# USB_DebugCable.net
KiCad netlist of a schematic drawn in EAGLE
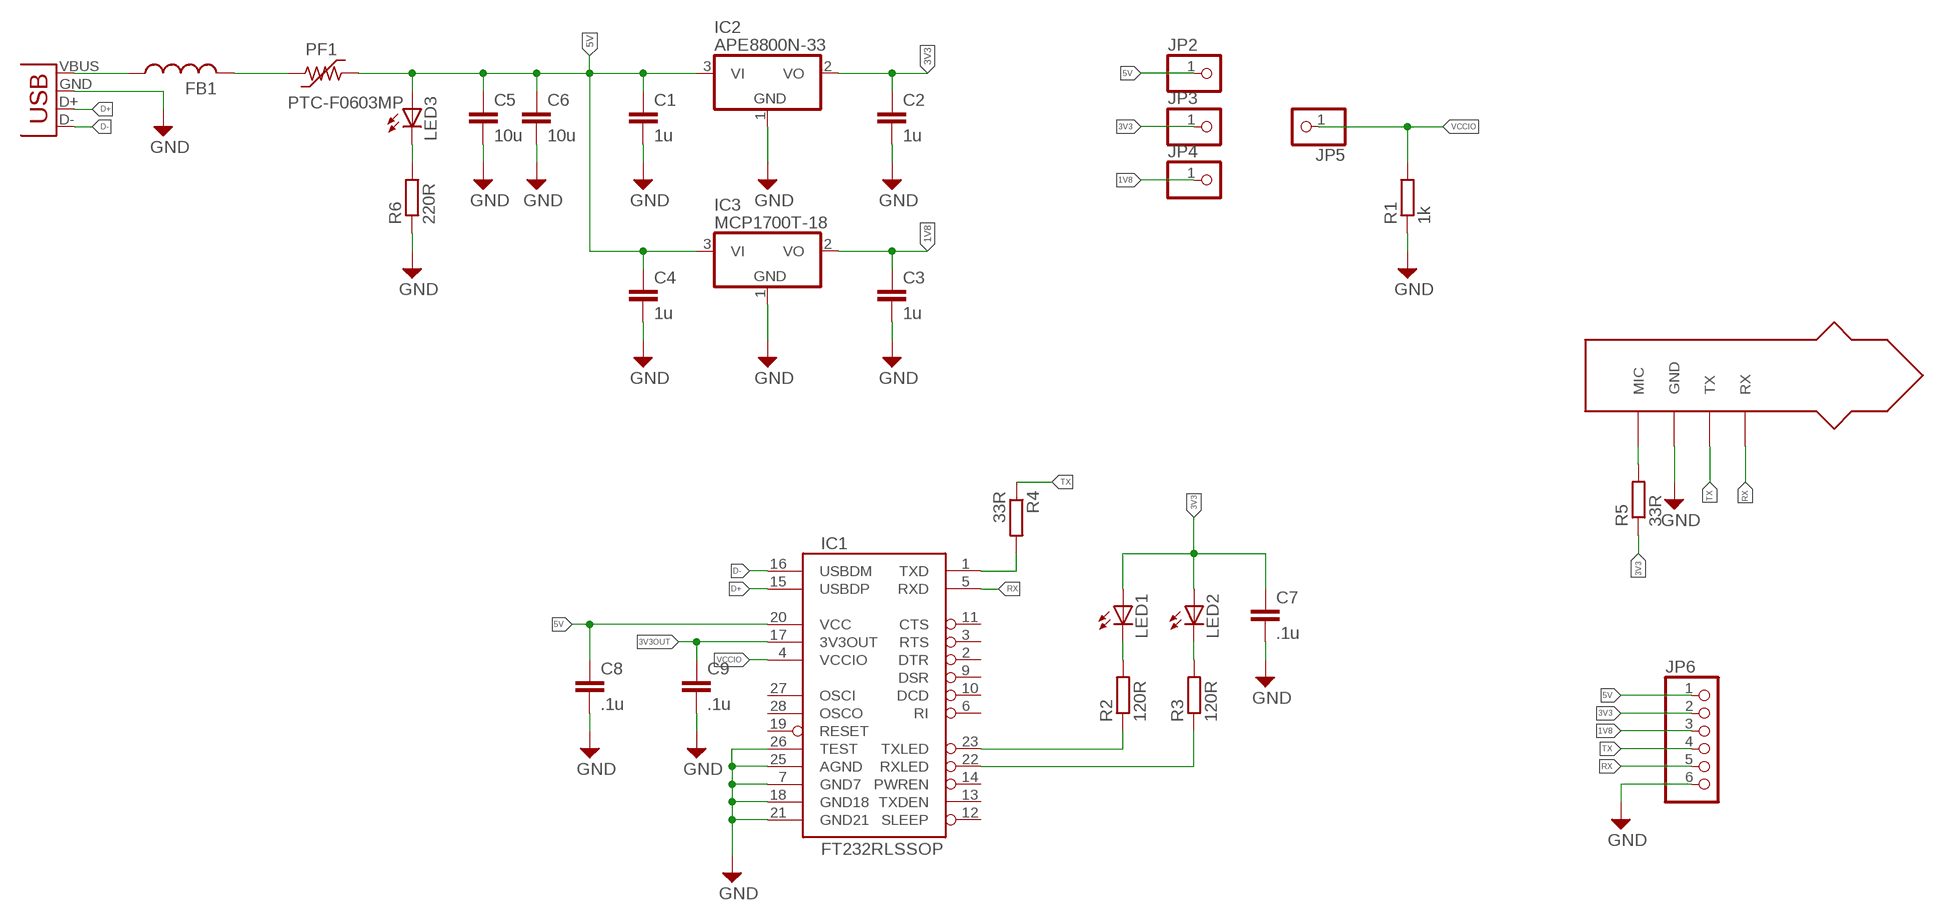
[diagram p0: schematic, sheet 1]

(export (version "E")
  (design (tool "Eeschema 10.0.6"))
  (components
    (comp (ref "C1")
      (value "1u")
      (footprint "eagle-import:C0603K")
      (libsource (lib "eagle-import") (part "C-EUC0603K"))
    )
    (comp (ref "C2")
      (value "1u")
      (footprint "eagle-import:C0603K")
      (libsource (lib "eagle-import") (part "C-EUC0603K"))
    )
    (comp (ref "C3")
      (value "1u")
      (footprint "eagle-import:C0603K")
      (libsource (lib "eagle-import") (part "C-EUC0603K"))
    )
    (comp (ref "C4")
      (value "1u")
      (footprint "eagle-import:C0603K")
      (libsource (lib "eagle-import") (part "C-EUC0603K"))
    )
    (comp (ref "C5")
      (value "10u")
      (footprint "eagle-import:C0603K")
      (libsource (lib "eagle-import") (part "C-EUC0603K"))
    )
    (comp (ref "C6")
      (value "10u")
      (footprint "eagle-import:C0603K")
      (libsource (lib "eagle-import") (part "C-EUC0603K"))
    )
    (comp (ref "C7")
      (value ".1u")
      (footprint "eagle-import:C0603K")
      (libsource (lib "eagle-import") (part "C-EUC0603K"))
    )
    (comp (ref "C8")
      (value ".1u")
      (footprint "eagle-import:C0402K")
      (libsource (lib "eagle-import") (part "C-EUC0402K"))
    )
    (comp (ref "C9")
      (value ".1u")
      (footprint "eagle-import:C0402K")
      (libsource (lib "eagle-import") (part "C-EUC0402K"))
    )
    (comp (ref "FB1")
      (value "FERRITE-BEADA")
      (footprint "eagle-import:0603")
      (libsource (lib "eagle-import") (part "FERRITE-BEADA"))
    )
    (comp (ref "IC1")
      (value "FT232RLSSOP")
      (footprint "eagle-import:SSOP28DB")
      (libsource (lib "eagle-import") (part "FT232RLSSOP"))
    )
    (comp (ref "IC2")
      (value "APE8800N-33")
      (footprint "eagle-import:SOT23")
      (libsource (lib "eagle-import") (part "MCP1703CB"))
    )
    (comp (ref "IC3")
      (value "MCP1700T-18")
      (footprint "eagle-import:SOT23")
      (libsource (lib "eagle-import") (part "MCP1703CB"))
    )
    (comp (ref "JP1")
      (value "USB-A-H")
      (footprint "eagle-import:USB-A-H")
      (libsource (lib "eagle-import") (part "USB-A-H"))
    )
    (comp (ref "JP2")
      (value "PINHD-1X1")
      (footprint "eagle-import:1X01")
      (libsource (lib "eagle-import") (part "PINHD-1X1"))
    )
    (comp (ref "JP3")
      (value "PINHD-1X1")
      (footprint "eagle-import:1X01")
      (libsource (lib "eagle-import") (part "PINHD-1X1"))
    )
    (comp (ref "JP4")
      (value "PINHD-1X1")
      (footprint "eagle-import:1X01")
      (libsource (lib "eagle-import") (part "PINHD-1X1"))
    )
    (comp (ref "JP5")
      (value "PINHD-1X1")
      (footprint "eagle-import:1X01")
      (libsource (lib "eagle-import") (part "PINHD-1X1"))
    )
    (comp (ref "JP6")
      (value "PINHD-1X6CB")
      (footprint "eagle-import:1X06-CLEANBIG")
      (libsource (lib "eagle-import") (part "PINHD-1X6CB"))
    )
    (comp (ref "LED1")
      (value "LEDCHIPLED_0603")
      (footprint "eagle-import:CHIPLED_0603")
      (libsource (lib "eagle-import") (part "LEDCHIPLED_0603"))
    )
    (comp (ref "LED2")
      (value "LEDCHIPLED_0603")
      (footprint "eagle-import:CHIPLED_0603")
      (libsource (lib "eagle-import") (part "LEDCHIPLED_0603"))
    )
    (comp (ref "LED3")
      (value "LEDCHIPLED_0603")
      (footprint "eagle-import:CHIPLED_0603")
      (libsource (lib "eagle-import") (part "LEDCHIPLED_0603"))
    )
    (comp (ref "PF1")
      (value "PTC-F0603MP")
      (footprint "eagle-import:F0603MP")
      (libsource (lib "eagle-import") (part "PTC-F0603MP"))
    )
    (comp (ref "R1")
      (value "1k")
      (footprint "eagle-import:R0603")
      (libsource (lib "eagle-import") (part "R-EU_R0603"))
    )
    (comp (ref "R2")
      (value "120R")
      (footprint "eagle-import:R0603")
      (libsource (lib "eagle-import") (part "R-EU_R0603"))
    )
    (comp (ref "R3")
      (value "120R")
      (footprint "eagle-import:R0603")
      (libsource (lib "eagle-import") (part "R-EU_R0603"))
    )
    (comp (ref "R4")
      (value "33R")
      (footprint "eagle-import:R0603")
      (libsource (lib "eagle-import") (part "R-EU_R0603"))
    )
    (comp (ref "R5")
      (value "33R")
      (footprint "eagle-import:R0603")
      (libsource (lib "eagle-import") (part "R-EU_R0603"))
    )
    (comp (ref "R6")
      (value "220R")
      (footprint "eagle-import:R0603")
      (libsource (lib "eagle-import") (part "R-EU_R0603"))
    )
    (comp (ref "U$1")
      (value "JACK3.5_4")
      (footprint "eagle-import:3.5MM4")
      (libsource (lib "eagle-import") (part "JACK3.5_4"))
    )
  )
  (nets
    (net (code "1") (name "1V8") (class "Default")
      (node (ref "C3") (pin "1") (pinfunction "1_1") (pintype "passive"))
      (node (ref "IC3") (pin "2") (pinfunction "VO_2") (pintype "passive"))
      (node (ref "JP4") (pin "1") (pinfunction "1_1") (pintype "passive"))
      (node (ref "JP6") (pin "3") (pinfunction "3_3") (pintype "passive"))
    )
    (net (code "2") (name "3V3") (class "Default")
      (node (ref "C2") (pin "1") (pinfunction "1_1") (pintype "passive"))
      (node (ref "C7") (pin "1") (pinfunction "1_1") (pintype "passive"))
      (node (ref "IC2") (pin "2") (pinfunction "VO_2") (pintype "passive"))
      (node (ref "JP3") (pin "1") (pinfunction "1_1") (pintype "passive"))
      (node (ref "JP6") (pin "2") (pinfunction "2_2") (pintype "passive"))
      (node (ref "LED1") (pin "A") (pinfunction "A_A") (pintype "passive"))
      (node (ref "LED2") (pin "A") (pinfunction "A_A") (pintype "passive"))
      (node (ref "R5") (pin "1") (pinfunction "1_1") (pintype "passive"))
    )
    (net (code "3") (name "3V3OUT") (class "Default")
      (node (ref "C9") (pin "1") (pinfunction "1_1") (pintype "passive"))
      (node (ref "IC1") (pin "17") (pinfunction "3V3OUT_17") (pintype "output"))
    )
    (net (code "4") (name "5V") (class "Default")
      (node (ref "C1") (pin "1") (pinfunction "1_1") (pintype "passive"))
      (node (ref "C4") (pin "1") (pinfunction "1_1") (pintype "passive"))
      (node (ref "C5") (pin "1") (pinfunction "1_1") (pintype "passive"))
      (node (ref "C6") (pin "1") (pinfunction "1_1") (pintype "passive"))
      (node (ref "C8") (pin "1") (pinfunction "1_1") (pintype "passive"))
      (node (ref "IC1") (pin "20") (pinfunction "VCC_20") (pintype "power_in"))
      (node (ref "IC2") (pin "3") (pinfunction "VI_3") (pintype "input"))
      (node (ref "IC3") (pin "3") (pinfunction "VI_3") (pintype "input"))
      (node (ref "JP2") (pin "1") (pinfunction "1_1") (pintype "passive"))
      (node (ref "JP6") (pin "1") (pinfunction "1_1") (pintype "passive"))
      (node (ref "LED3") (pin "A") (pinfunction "A_A") (pintype "passive"))
      (node (ref "PF1") (pin "2") (pinfunction "2_2") (pintype "passive"))
    )
    (net (code "5") (name "D+") (class "Default")
      (node (ref "IC1") (pin "15") (pinfunction "USBDP_15") (pintype "bidirectional"))
      (node (ref "JP1") (pin "D+") (pinfunction "D-_D+") (pintype "bidirectional"))
    )
    (net (code "6") (name "D-") (class "Default")
      (node (ref "IC1") (pin "16") (pinfunction "USBDM_16") (pintype "bidirectional"))
      (node (ref "JP1") (pin "D-") (pinfunction "D+_D-") (pintype "bidirectional"))
    )
    (net (code "7") (name "GND") (class "Default")
      (node (ref "C1") (pin "2") (pinfunction "2_2") (pintype "passive"))
      (node (ref "C2") (pin "2") (pinfunction "2_2") (pintype "passive"))
      (node (ref "C3") (pin "2") (pinfunction "2_2") (pintype "passive"))
      (node (ref "C4") (pin "2") (pinfunction "2_2") (pintype "passive"))
      (node (ref "C5") (pin "2") (pinfunction "2_2") (pintype "passive"))
      (node (ref "C6") (pin "2") (pinfunction "2_2") (pintype "passive"))
      (node (ref "C7") (pin "2") (pinfunction "2_2") (pintype "passive"))
      (node (ref "C8") (pin "2") (pinfunction "2_2") (pintype "passive"))
      (node (ref "C9") (pin "2") (pinfunction "2_2") (pintype "passive"))
      (node (ref "IC1") (pin "18") (pinfunction "GND18_18") (pintype "power_in"))
      (node (ref "IC1") (pin "21") (pinfunction "GND21_21") (pintype "power_in"))
      (node (ref "IC1") (pin "25") (pinfunction "AGND_25") (pintype "power_in"))
      (node (ref "IC1") (pin "26") (pinfunction "TEST_26") (pintype "input"))
      (node (ref "IC1") (pin "7") (pinfunction "GND7_7") (pintype "power_in"))
      (node (ref "IC2") (pin "1") (pinfunction "GND_1") (pintype "passive"))
      (node (ref "IC3") (pin "1") (pinfunction "GND_1") (pintype "passive"))
      (node (ref "JP1") (pin "GND") (pinfunction "VBUS_GND") (pintype "bidirectional"))
      (node (ref "JP6") (pin "6") (pinfunction "6_6") (pintype "passive"))
      (node (ref "R1") (pin "1") (pinfunction "1_1") (pintype "passive"))
      (node (ref "R6") (pin "1") (pinfunction "1_1") (pintype "passive"))
      (node (ref "U$1") (pin "GND") (pinfunction "GND_GND") (pintype "bidirectional"))
    )
    (net (code "8") (name "Net-(FB1-Pad2)") (class "Default")
      (node (ref "FB1") (pin "2") (pinfunction "2_2") (pintype "passive"))
      (node (ref "PF1") (pin "1") (pinfunction "1_1") (pintype "passive"))
    )
    (net (code "9") (name "Net-(IC1-RXLED)") (class "Default")
      (node (ref "IC1") (pin "22") (pinfunction "RXLED_22") (pintype "input"))
      (node (ref "R3") (pin "1") (pinfunction "1_1") (pintype "passive"))
    )
    (net (code "10") (name "Net-(IC1-TXD)") (class "Default")
      (node (ref "IC1") (pin "1") (pinfunction "TXD_1") (pintype "output"))
      (node (ref "R4") (pin "2") (pinfunction "2_2") (pintype "passive"))
    )
    (net (code "11") (name "Net-(IC1-TXLED)") (class "Default")
      (node (ref "IC1") (pin "23") (pinfunction "TXLED_23") (pintype "input"))
      (node (ref "R2") (pin "1") (pinfunction "1_1") (pintype "passive"))
    )
    (net (code "12") (name "Net-(JP1-GND)") (class "Default")
      (node (ref "FB1") (pin "1") (pinfunction "1_1") (pintype "passive"))
      (node (ref "JP1") (pin "VBUS") (pinfunction "GND_VBUS") (pintype "bidirectional"))
    )
    (net (code "13") (name "Net-(LED1-PadC)") (class "Default")
      (node (ref "LED1") (pin "C") (pinfunction "C_C") (pintype "passive"))
      (node (ref "R2") (pin "2") (pinfunction "2_2") (pintype "passive"))
    )
    (net (code "14") (name "Net-(LED2-PadC)") (class "Default")
      (node (ref "LED2") (pin "C") (pinfunction "C_C") (pintype "passive"))
      (node (ref "R3") (pin "2") (pinfunction "2_2") (pintype "passive"))
    )
    (net (code "15") (name "Net-(LED3-PadC)") (class "Default")
      (node (ref "LED3") (pin "C") (pinfunction "C_C") (pintype "passive"))
      (node (ref "R6") (pin "2") (pinfunction "2_2") (pintype "passive"))
    )
    (net (code "16") (name "Net-(R5-Pad2)") (class "Default")
      (node (ref "R5") (pin "2") (pinfunction "2_2") (pintype "passive"))
      (node (ref "U$1") (pin "MIC_1") (pinfunction "MIC_MIC_1") (pintype "bidirectional"))
      (node (ref "U$1") (pin "MIC_2") (pinfunction "MIC_MIC_2") (pintype "bidirectional"))
    )
    (net (code "17") (name "RX") (class "Default")
      (node (ref "IC1") (pin "5") (pinfunction "RXD_5") (pintype "input"))
      (node (ref "JP6") (pin "5") (pinfunction "5_5") (pintype "passive"))
      (node (ref "U$1") (pin "RX_1") (pinfunction "RX_RX_1") (pintype "bidirectional"))
      (node (ref "U$1") (pin "RX_2") (pinfunction "RX_RX_2") (pintype "bidirectional"))
    )
    (net (code "18") (name "TX") (class "Default")
      (node (ref "JP6") (pin "4") (pinfunction "4_4") (pintype "passive"))
      (node (ref "R4") (pin "1") (pinfunction "1_1") (pintype "passive"))
      (node (ref "U$1") (pin "TX") (pinfunction "TX_TX") (pintype "bidirectional"))
    )
    (net (code "19") (name "VCCIO") (class "Default")
      (node (ref "IC1") (pin "4") (pinfunction "VCCIO_4") (pintype "power_in"))
      (node (ref "JP5") (pin "1") (pinfunction "1_1") (pintype "passive"))
      (node (ref "R1") (pin "2") (pinfunction "2_2") (pintype "passive"))
    )
    (net (code "20") (name "unconnected-(IC1-CTS-Pad11)") (class "Default")
      (node (ref "IC1") (pin "11") (pinfunction "CTS_11") (pintype "input"))
    )
    (net (code "21") (name "unconnected-(IC1-DCD-Pad10)") (class "Default")
      (node (ref "IC1") (pin "10") (pinfunction "DCD_10") (pintype "input"))
    )
    (net (code "22") (name "unconnected-(IC1-DSR-Pad9)") (class "Default")
      (node (ref "IC1") (pin "9") (pinfunction "DSR_9") (pintype "input"))
    )
    (net (code "23") (name "unconnected-(IC1-DTR-Pad2)") (class "Default")
      (node (ref "IC1") (pin "2") (pinfunction "DTR_2") (pintype "output"))
    )
    (net (code "24") (name "unconnected-(IC1-OSCI-Pad27)") (class "Default")
      (node (ref "IC1") (pin "27") (pinfunction "OSCI_27") (pintype "input"))
    )
    (net (code "25") (name "unconnected-(IC1-OSCO-Pad28)") (class "Default")
      (node (ref "IC1") (pin "28") (pinfunction "OSCO_28") (pintype "output"))
    )
    (net (code "26") (name "unconnected-(IC1-PWREN-Pad14)") (class "Default")
      (node (ref "IC1") (pin "14") (pinfunction "PWREN_14") (pintype "input"))
    )
    (net (code "27") (name "unconnected-(IC1-RESET-Pad19)") (class "Default")
      (node (ref "IC1") (pin "19") (pinfunction "RESET_19") (pintype "input"))
    )
    (net (code "28") (name "unconnected-(IC1-RI-Pad6)") (class "Default")
      (node (ref "IC1") (pin "6") (pinfunction "RI_6") (pintype "input"))
    )
    (net (code "29") (name "unconnected-(IC1-RTS-Pad3)") (class "Default")
      (node (ref "IC1") (pin "3") (pinfunction "RTS_3") (pintype "output"))
    )
    (net (code "30") (name "unconnected-(IC1-SLEEP-Pad12)") (class "Default")
      (node (ref "IC1") (pin "12") (pinfunction "SLEEP_12") (pintype "input"))
    )
    (net (code "31") (name "unconnected-(IC1-TXDEN-Pad13)") (class "Default")
      (node (ref "IC1") (pin "13") (pinfunction "TXDEN_13") (pintype "input"))
    )
  )
)
